# schematic.net
KiCad netlist of a schematic drawn in EAGLE
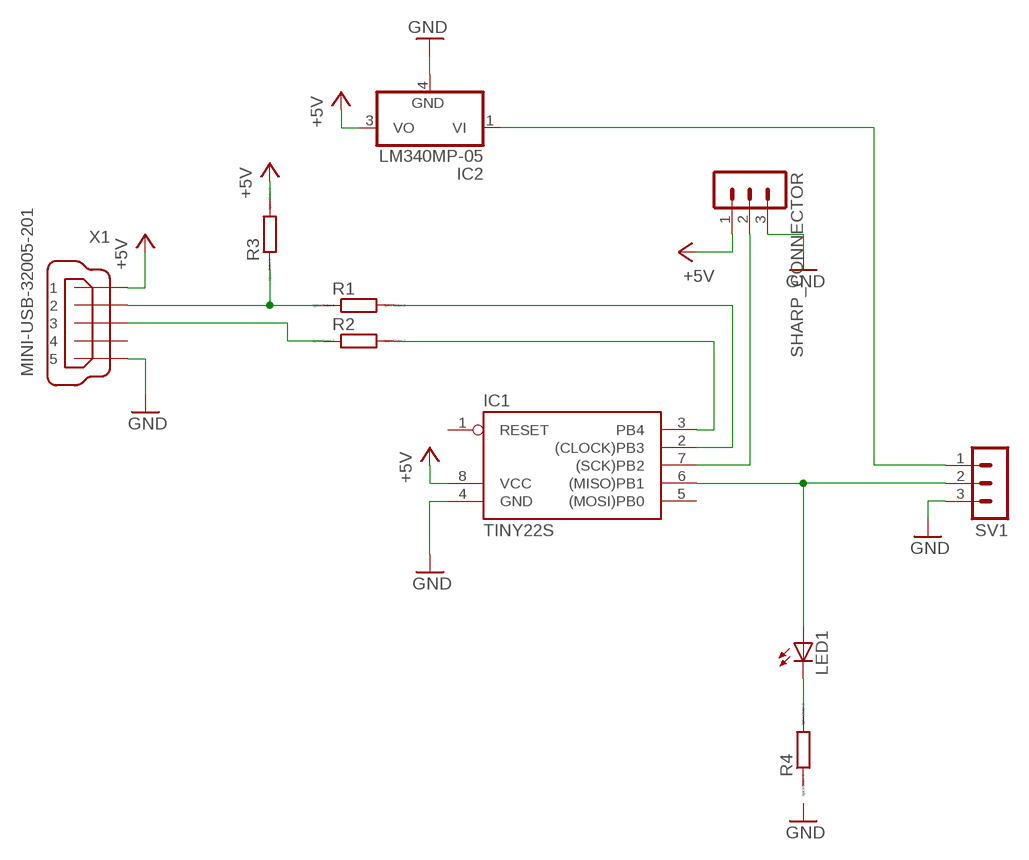
[diagram p0: schematic, sheet 1]

(export (version "E")
  (design (tool "Eeschema 10.0.6"))
  (components
    (comp (ref "IC1")
      (value "TINY22S")
      (footprint "eagle-import:SOIC8")
      (libsource (lib "eagle-import") (part "TINY22S"))
    )
    (comp (ref "IC2")
      (value "LM340MP-05")
      (footprint "eagle-import:SOT223")
      (libsource (lib "eagle-import") (part "LM340?-MP05"))
    )
    (comp (ref "LED1")
      (value "LEDCHIP-LED0603")
      (footprint "eagle-import:CHIP-LED0603")
      (libsource (lib "eagle-import") (part "LEDCHIP-LED0603"))
    )
    (comp (ref "R1")
      (value "RR0603")
      (footprint "eagle-import:R0603")
      (libsource (lib "eagle-import") (part "RR0603"))
    )
    (comp (ref "R2")
      (value "RR0603")
      (footprint "eagle-import:R0603")
      (libsource (lib "eagle-import") (part "RR0603"))
    )
    (comp (ref "R3")
      (value "RR0603")
      (footprint "eagle-import:R0603")
      (libsource (lib "eagle-import") (part "RR0603"))
    )
    (comp (ref "R4")
      (value "RR0603")
      (footprint "eagle-import:R0603")
      (libsource (lib "eagle-import") (part "RR0603"))
    )
    (comp (ref "SHARP_CONNECTOR")
      (value "MA03-1")
      (footprint "eagle-import:MA03-1")
      (libsource (lib "eagle-import") (part "MA03-1"))
    )
    (comp (ref "SV1")
      (value "MA03-1")
      (footprint "eagle-import:MA03-1")
      (libsource (lib "eagle-import") (part "MA03-1"))
    )
    (comp (ref "X1")
      (value "MINI-USB-32005-201")
      (footprint "eagle-import:32005-201")
      (libsource (lib "eagle-import") (part "MINI-USB-32005-201"))
    )
  )
  (nets
    (net (code "1") (name "+5V") (class "Default")
      (node (ref "IC1") (pin "8") (pinfunction "VCC_8") (pintype "power_in"))
      (node (ref "IC2") (pin "3") (pinfunction "VO_3") (pintype "passive"))
      (node (ref "R3") (pin "2") (pinfunction "2_2") (pintype "passive"))
      (node (ref "SHARP_CONNECTOR") (pin "1") (pinfunction "1_1") (pintype "passive"))
      (node (ref "X1") (pin "1") (pinfunction "1_1") (pintype "passive"))
    )
    (net (code "2") (name "GND") (class "Default")
      (node (ref "IC1") (pin "4") (pinfunction "GND_4") (pintype "power_in"))
      (node (ref "IC2") (pin "4") (pinfunction "GND_4") (pintype "passive"))
      (node (ref "SHARP_CONNECTOR") (pin "3") (pinfunction "3_3") (pintype "passive"))
      (node (ref "SV1") (pin "3") (pinfunction "3_3") (pintype "passive"))
      (node (ref "X1") (pin "5") (pinfunction "5_5") (pintype "passive"))
    )
    (net (code "3") (name "Net-(IC1-(CLOCK)PB3)") (class "Default")
      (node (ref "IC1") (pin "2") (pinfunction "(CLOCK)PB3_2") (pintype "bidirectional"))
      (node (ref "R1") (pin "2") (pinfunction "2_2") (pintype "passive"))
    )
    (net (code "4") (name "Net-(IC1-(MISO)PB1)") (class "Default")
      (node (ref "IC1") (pin "6") (pinfunction "(MISO)PB1_6") (pintype "bidirectional"))
      (node (ref "LED1") (pin "A") (pinfunction "A_A") (pintype "passive"))
      (node (ref "SV1") (pin "2") (pinfunction "2_2") (pintype "passive"))
    )
    (net (code "5") (name "Net-(IC1-(SCK)PB2)") (class "Default")
      (node (ref "IC1") (pin "7") (pinfunction "(SCK)PB2_7") (pintype "bidirectional"))
      (node (ref "SHARP_CONNECTOR") (pin "2") (pinfunction "2_2") (pintype "passive"))
    )
    (net (code "6") (name "Net-(IC1-PB4)") (class "Default")
      (node (ref "IC1") (pin "3") (pinfunction "PB4_3") (pintype "bidirectional"))
      (node (ref "R2") (pin "2") (pinfunction "2_2") (pintype "passive"))
    )
    (net (code "7") (name "Net-(IC2-VI)") (class "Default")
      (node (ref "IC2") (pin "1") (pinfunction "VI_1") (pintype "input"))
      (node (ref "SV1") (pin "1") (pinfunction "1_1") (pintype "passive"))
    )
    (net (code "8") (name "Net-(LED1-PadC)") (class "Default")
      (node (ref "LED1") (pin "C") (pinfunction "C_C") (pintype "passive"))
      (node (ref "R4") (pin "2") (pinfunction "2_2") (pintype "passive"))
    )
    (net (code "9") (name "Net-(R1-Pad1)") (class "Default")
      (node (ref "R1") (pin "1") (pinfunction "1_1") (pintype "passive"))
      (node (ref "R3") (pin "1") (pinfunction "1_1") (pintype "passive"))
      (node (ref "X1") (pin "2") (pinfunction "2_2") (pintype "passive"))
    )
    (net (code "10") (name "Net-(R2-Pad1)") (class "Default")
      (node (ref "R2") (pin "1") (pinfunction "1_1") (pintype "passive"))
      (node (ref "X1") (pin "3") (pinfunction "3_3") (pintype "passive"))
    )
    (net (code "11") (name "unconnected-(IC1-(MOSI)PB0-Pad5)") (class "Default")
      (node (ref "IC1") (pin "5") (pinfunction "(MOSI)PB0_5") (pintype "bidirectional"))
    )
    (net (code "12") (name "unconnected-(IC1-RESET-Pad1)") (class "Default")
      (node (ref "IC1") (pin "1") (pinfunction "RESET_1") (pintype "input"))
    )
    (net (code "13") (name "unconnected-(R4-Pad1)") (class "Default")
      (node (ref "R4") (pin "1") (pinfunction "1_1") (pintype "passive"))
    )
    (net (code "14") (name "unconnected-(X1-Pad4)") (class "Default")
      (node (ref "X1") (pin "4") (pinfunction "4_4") (pintype "passive"))
    )
  )
)
